# PFC_breakout_v2b.net
KiCad netlist of a schematic drawn in EAGLE
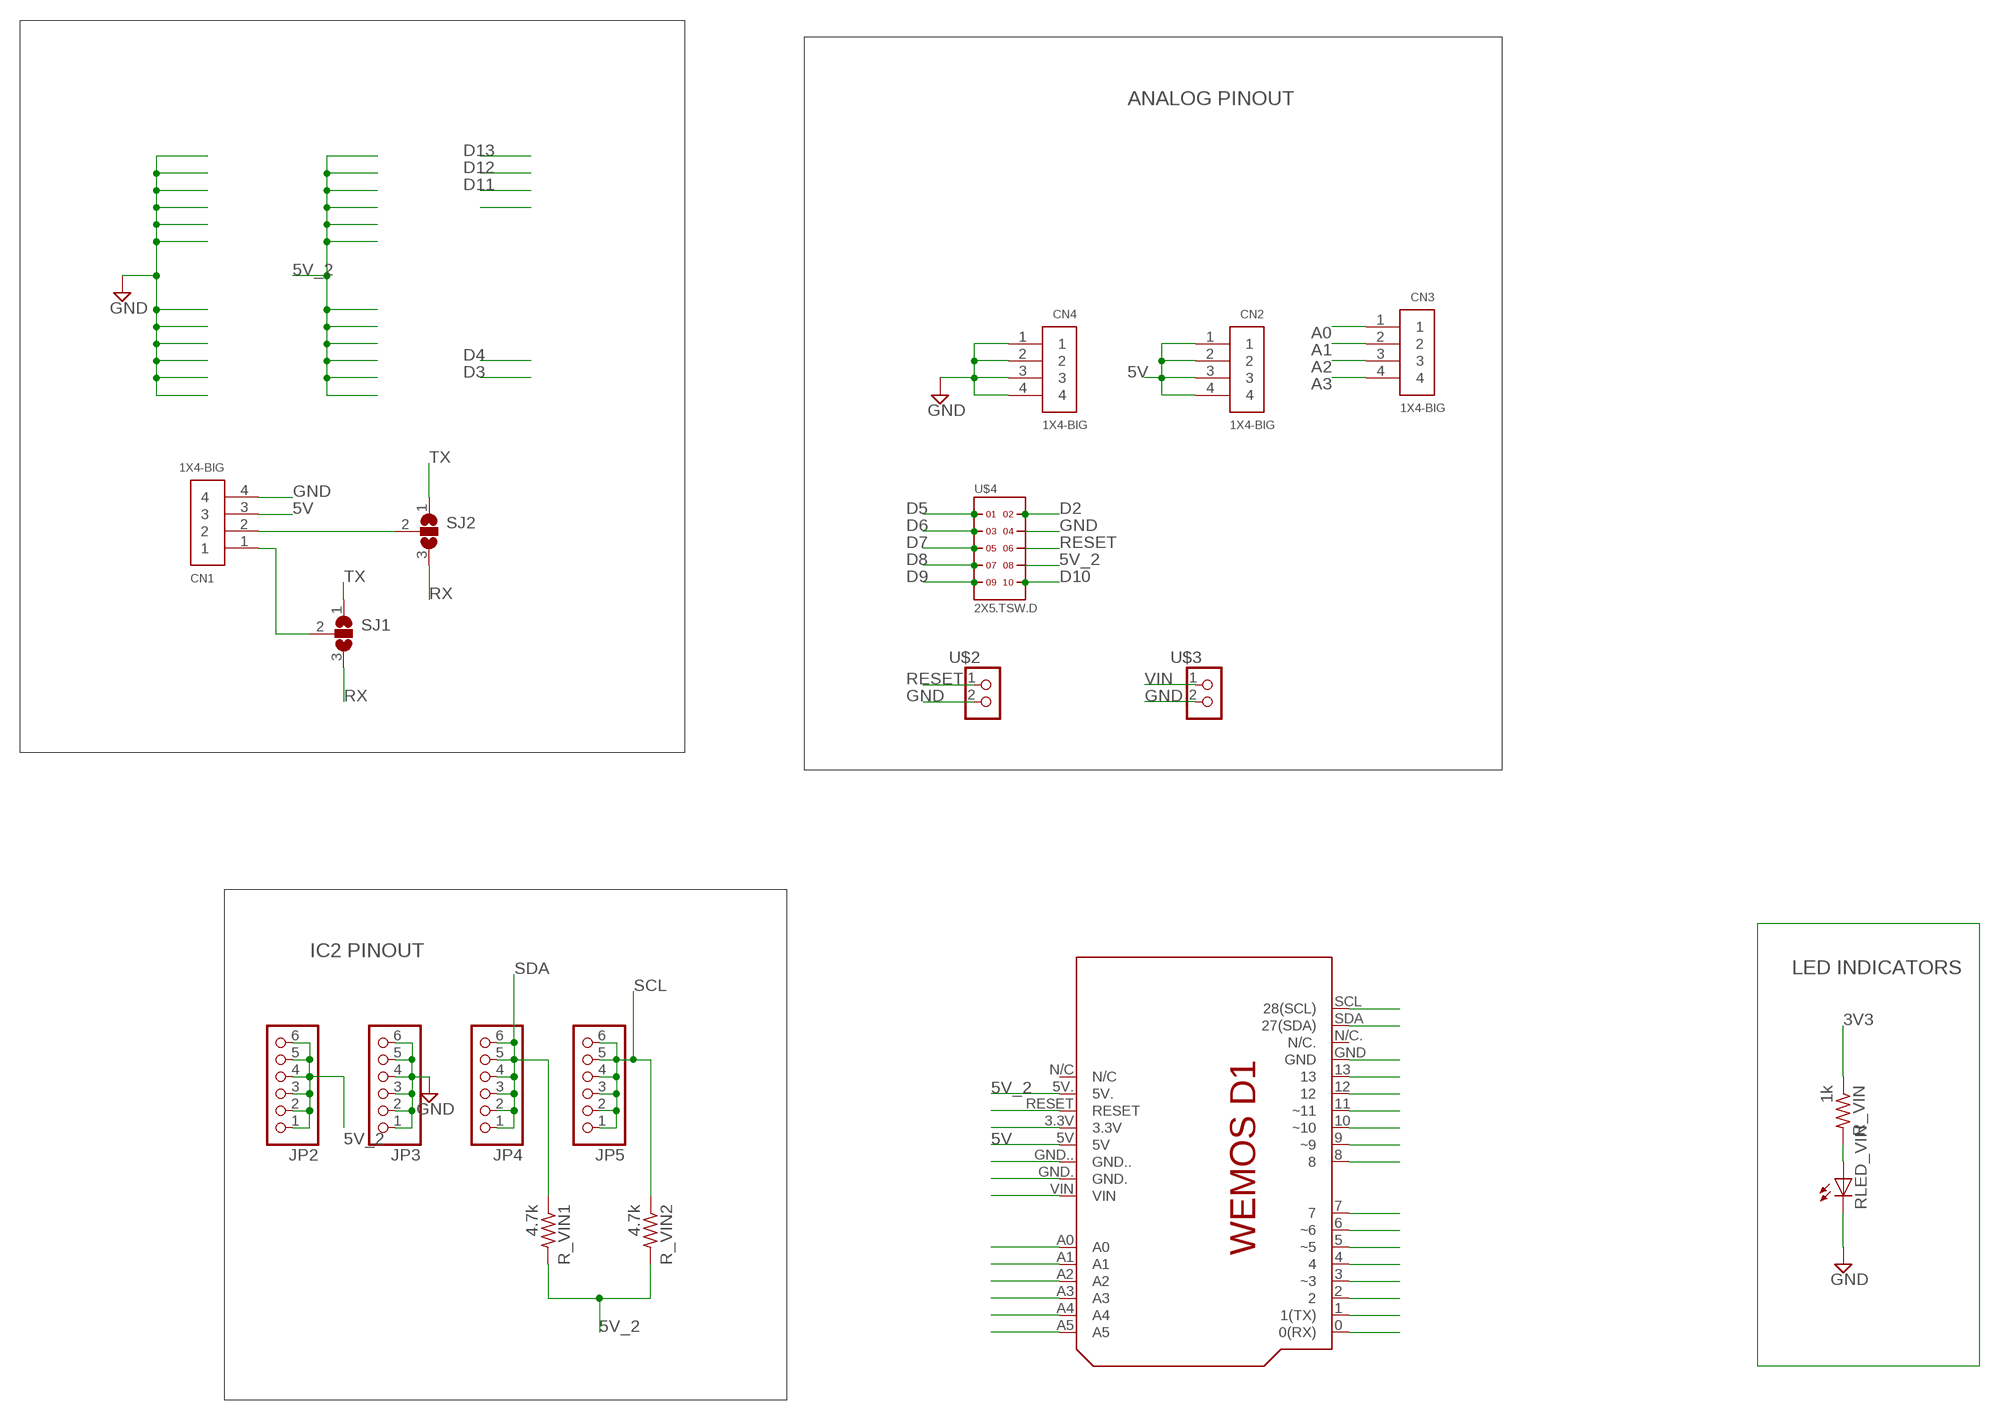
[diagram p0: schematic, sheet 1]

(export (version "E")
  (design (tool "Eeschema 10.0.6"))
  (components
    (comp (ref "CN1")
      (value "1X4-BIG")
      (footprint "eagle-import:1X04-BIG")
      (libsource (lib "eagle-import") (part "1X4-BIG"))
    )
    (comp (ref "CN2")
      (value "1X4-BIG")
      (footprint "eagle-import:1X04-BIG")
      (libsource (lib "eagle-import") (part "1X4-BIG"))
    )
    (comp (ref "CN3")
      (value "1X4-BIG")
      (footprint "eagle-import:1X04-BIG")
      (libsource (lib "eagle-import") (part "1X4-BIG"))
    )
    (comp (ref "CN4")
      (value "1X4-BIG")
      (footprint "eagle-import:1X04-BIG")
      (libsource (lib "eagle-import") (part "1X4-BIG"))
    )
    (comp (ref "JP2")
      (value "PINHD-1X6")
      (footprint "eagle-import:1X06")
      (libsource (lib "eagle-import") (part "PINHD-1X6"))
    )
    (comp (ref "JP3")
      (value "PINHD-1X6")
      (footprint "eagle-import:1X06")
      (libsource (lib "eagle-import") (part "PINHD-1X6"))
    )
    (comp (ref "JP4")
      (value "PINHD-1X6")
      (footprint "eagle-import:1X06")
      (libsource (lib "eagle-import") (part "PINHD-1X6"))
    )
    (comp (ref "JP5")
      (value "PINHD-1X6")
      (footprint "eagle-import:1X06")
      (libsource (lib "eagle-import") (part "PINHD-1X6"))
    )
    (comp (ref "RLED_VIN")
      (value "LEDCHIP-LED0603")
      (footprint "eagle-import:CHIP-LED0603")
      (libsource (lib "eagle-import") (part "LEDCHIP-LED0603"))
    )
    (comp (ref "R_VIN")
      (value "1k")
      (footprint "eagle-import:R0603")
      (libsource (lib "eagle-import") (part "R-US_R0603"))
    )
    (comp (ref "R_VIN1")
      (value "4.7k")
      (footprint "eagle-import:R0603")
      (libsource (lib "eagle-import") (part "R-US_R0603"))
    )
    (comp (ref "R_VIN2")
      (value "4.7k")
      (footprint "eagle-import:R0603")
      (libsource (lib "eagle-import") (part "R-US_R0603"))
    )
    (comp (ref "SJ1")
      (value "SJ2W")
      (footprint "eagle-import:SJ_2")
      (libsource (lib "eagle-import") (part "SJ2W"))
    )
    (comp (ref "SJ2")
      (value "SJ2W")
      (footprint "eagle-import:SJ_2")
      (libsource (lib "eagle-import") (part "SJ2W"))
    )
    (comp (ref "U$1")
      (value "WEMOS-D1SHIELD")
      (footprint "eagle-import:WEMOS-D1")
      (libsource (lib "eagle-import") (part "WEMOS-D1SHIELD"))
    )
    (comp (ref "U$2")
      (value "PINHD-2X1")
      (footprint "eagle-import:2X01")
      (libsource (lib "eagle-import") (part "PINHD-2X1"))
    )
    (comp (ref "U$3")
      (value "PINHD-2X1")
      (footprint "eagle-import:2X01")
      (libsource (lib "eagle-import") (part "PINHD-2X1"))
    )
    (comp (ref "U$4")
      (value "2X5.TSW.D")
      (footprint "eagle-import:TSW-105-XXX-D-XXX")
      (libsource (lib "eagle-import") (part "2X5.TSW.D"))
    )
  )
  (nets
    (net (code "1") (name "/3V3") (class "Default")
      (node (ref "R_VIN") (pin "1") (pinfunction "1_1") (pintype "passive"))
      (node (ref "U$1") (pin "3.3V") (pinfunction "3.3V_3.3V") (pintype "bidirectional"))
    )
    (net (code "2") (name "/5V") (class "Default")
      (node (ref "CN1") (pin "3") (pinfunction "3_3") (pintype "bidirectional"))
      (node (ref "CN2") (pin "1") (pinfunction "1_1") (pintype "bidirectional"))
      (node (ref "CN2") (pin "2") (pinfunction "2_2") (pintype "bidirectional"))
      (node (ref "CN2") (pin "3") (pinfunction "3_3") (pintype "bidirectional"))
      (node (ref "CN2") (pin "4") (pinfunction "4_4") (pintype "bidirectional"))
      (node (ref "U$1") (pin "5V") (pinfunction "5V_5V") (pintype "bidirectional"))
    )
    (net (code "3") (name "/5V_2") (class "Default")
      (node (ref "JP2") (pin "1") (pinfunction "1_1") (pintype "passive"))
      (node (ref "JP2") (pin "2") (pinfunction "2_2") (pintype "passive"))
      (node (ref "JP2") (pin "3") (pinfunction "3_3") (pintype "passive"))
      (node (ref "JP2") (pin "4") (pinfunction "4_4") (pintype "passive"))
      (node (ref "JP2") (pin "5") (pinfunction "5_5") (pintype "passive"))
      (node (ref "JP2") (pin "6") (pinfunction "6_6") (pintype "passive"))
      (node (ref "R_VIN1") (pin "2") (pinfunction "2_2") (pintype "passive"))
      (node (ref "R_VIN2") (pin "2") (pinfunction "2_2") (pintype "passive"))
      (node (ref "U$1") (pin "5V.") (pinfunction "5V._5V.") (pintype "bidirectional"))
      (node (ref "U$4") (pin "8") (pinfunction "8_8") (pintype "bidirectional"))
    )
    (net (code "4") (name "/A0") (class "Default")
      (node (ref "CN3") (pin "1") (pinfunction "1_1") (pintype "bidirectional"))
      (node (ref "U$1") (pin "A0") (pinfunction "A0_A0") (pintype "bidirectional"))
    )
    (net (code "5") (name "/A1") (class "Default")
      (node (ref "CN3") (pin "2") (pinfunction "2_2") (pintype "bidirectional"))
      (node (ref "U$1") (pin "A1") (pinfunction "A1_A1") (pintype "bidirectional"))
    )
    (net (code "6") (name "/A2") (class "Default")
      (node (ref "CN3") (pin "3") (pinfunction "3_3") (pintype "bidirectional"))
      (node (ref "U$1") (pin "A2") (pinfunction "A2_A2") (pintype "bidirectional"))
    )
    (net (code "7") (name "/A3") (class "Default")
      (node (ref "CN3") (pin "4") (pinfunction "4_4") (pintype "bidirectional"))
      (node (ref "U$1") (pin "A3") (pinfunction "A3_A3") (pintype "bidirectional"))
    )
    (net (code "8") (name "/D2") (class "Default")
      (node (ref "U$1") (pin "2") (pinfunction "2_2") (pintype "bidirectional"))
      (node (ref "U$4") (pin "2") (pinfunction "2_2") (pintype "bidirectional"))
    )
    (net (code "9") (name "/D3") (class "Default")
      (node (ref "U$1") (pin "3") (pinfunction "~{3}_3") (pintype "bidirectional"))
    )
    (net (code "10") (name "/D4") (class "Default")
      (node (ref "U$1") (pin "4") (pinfunction "4_4") (pintype "bidirectional"))
    )
    (net (code "11") (name "/D5") (class "Default")
      (node (ref "U$1") (pin "5") (pinfunction "~{5}_5") (pintype "bidirectional"))
      (node (ref "U$4") (pin "1") (pinfunction "1_1") (pintype "bidirectional"))
    )
    (net (code "12") (name "/D6") (class "Default")
      (node (ref "U$1") (pin "6") (pinfunction "~{6}_6") (pintype "bidirectional"))
      (node (ref "U$4") (pin "3") (pinfunction "3_3") (pintype "bidirectional"))
    )
    (net (code "13") (name "/D7") (class "Default")
      (node (ref "U$1") (pin "7") (pinfunction "7_7") (pintype "bidirectional"))
      (node (ref "U$4") (pin "5") (pinfunction "5_5") (pintype "bidirectional"))
    )
    (net (code "14") (name "/D8") (class "Default")
      (node (ref "U$1") (pin "8") (pinfunction "8_8") (pintype "bidirectional"))
      (node (ref "U$4") (pin "7") (pinfunction "7_7") (pintype "bidirectional"))
    )
    (net (code "15") (name "/D9") (class "Default")
      (node (ref "U$1") (pin "9") (pinfunction "~{9}_9") (pintype "bidirectional"))
      (node (ref "U$4") (pin "9") (pinfunction "9_9") (pintype "bidirectional"))
    )
    (net (code "16") (name "/D10") (class "Default")
      (node (ref "U$1") (pin "10") (pinfunction "~{10}_10") (pintype "bidirectional"))
      (node (ref "U$4") (pin "10") (pinfunction "10_10") (pintype "bidirectional"))
    )
    (net (code "17") (name "/D11") (class "Default")
      (node (ref "U$1") (pin "11") (pinfunction "~{11}_11") (pintype "bidirectional"))
    )
    (net (code "18") (name "/D12") (class "Default")
      (node (ref "U$1") (pin "12") (pinfunction "12_12") (pintype "bidirectional"))
    )
    (net (code "19") (name "/D13") (class "Default")
      (node (ref "U$1") (pin "13") (pinfunction "13_13") (pintype "bidirectional"))
    )
    (net (code "20") (name "/RESET") (class "Default")
      (node (ref "U$1") (pin "RESET") (pinfunction "RESET_RESET") (pintype "bidirectional"))
      (node (ref "U$2") (pin "1") (pinfunction "1_1") (pintype "passive"))
      (node (ref "U$4") (pin "6") (pinfunction "6_6") (pintype "bidirectional"))
    )
    (net (code "21") (name "/RX") (class "Default")
      (node (ref "SJ1") (pin "3") (pinfunction "3_3") (pintype "passive"))
      (node (ref "SJ2") (pin "3") (pinfunction "3_3") (pintype "passive"))
      (node (ref "U$1") (pin "0") (pinfunction "0(RX)_0") (pintype "bidirectional"))
    )
    (net (code "22") (name "/SCL") (class "Default")
      (node (ref "JP5") (pin "1") (pinfunction "1_1") (pintype "passive"))
      (node (ref "JP5") (pin "2") (pinfunction "2_2") (pintype "passive"))
      (node (ref "JP5") (pin "3") (pinfunction "3_3") (pintype "passive"))
      (node (ref "JP5") (pin "4") (pinfunction "4_4") (pintype "passive"))
      (node (ref "JP5") (pin "5") (pinfunction "5_5") (pintype "passive"))
      (node (ref "JP5") (pin "6") (pinfunction "6_6") (pintype "passive"))
      (node (ref "R_VIN2") (pin "1") (pinfunction "1_1") (pintype "passive"))
      (node (ref "U$1") (pin "SCL") (pinfunction "28(SCL)_SCL") (pintype "bidirectional"))
    )
    (net (code "23") (name "/SDA") (class "Default")
      (node (ref "JP4") (pin "1") (pinfunction "1_1") (pintype "passive"))
      (node (ref "JP4") (pin "2") (pinfunction "2_2") (pintype "passive"))
      (node (ref "JP4") (pin "3") (pinfunction "3_3") (pintype "passive"))
      (node (ref "JP4") (pin "4") (pinfunction "4_4") (pintype "passive"))
      (node (ref "JP4") (pin "5") (pinfunction "5_5") (pintype "passive"))
      (node (ref "JP4") (pin "6") (pinfunction "6_6") (pintype "passive"))
      (node (ref "R_VIN1") (pin "1") (pinfunction "1_1") (pintype "passive"))
      (node (ref "U$1") (pin "SDA") (pinfunction "27(SDA)_SDA") (pintype "bidirectional"))
    )
    (net (code "24") (name "/TX") (class "Default")
      (node (ref "SJ1") (pin "1") (pinfunction "1_1") (pintype "passive"))
      (node (ref "SJ2") (pin "1") (pinfunction "1_1") (pintype "passive"))
      (node (ref "U$1") (pin "1") (pinfunction "1(TX)_1") (pintype "bidirectional"))
    )
    (net (code "25") (name "/VIN") (class "Default")
      (node (ref "U$1") (pin "VIN") (pinfunction "VIN_VIN") (pintype "bidirectional"))
      (node (ref "U$3") (pin "1") (pinfunction "1_1") (pintype "passive"))
    )
    (net (code "26") (name "GND") (class "Default")
      (node (ref "CN1") (pin "4") (pinfunction "4_4") (pintype "bidirectional"))
      (node (ref "CN4") (pin "1") (pinfunction "1_1") (pintype "bidirectional"))
      (node (ref "CN4") (pin "2") (pinfunction "2_2") (pintype "bidirectional"))
      (node (ref "CN4") (pin "3") (pinfunction "3_3") (pintype "bidirectional"))
      (node (ref "CN4") (pin "4") (pinfunction "4_4") (pintype "bidirectional"))
      (node (ref "JP3") (pin "1") (pinfunction "1_1") (pintype "passive"))
      (node (ref "JP3") (pin "2") (pinfunction "2_2") (pintype "passive"))
      (node (ref "JP3") (pin "3") (pinfunction "3_3") (pintype "passive"))
      (node (ref "JP3") (pin "4") (pinfunction "4_4") (pintype "passive"))
      (node (ref "JP3") (pin "5") (pinfunction "5_5") (pintype "passive"))
      (node (ref "JP3") (pin "6") (pinfunction "6_6") (pintype "passive"))
      (node (ref "RLED_VIN") (pin "C") (pinfunction "C_C") (pintype "passive"))
      (node (ref "U$1") (pin "GND") (pinfunction "GND_GND") (pintype "bidirectional"))
      (node (ref "U$1") (pin "GND.") (pinfunction "GND._GND.") (pintype "bidirectional"))
      (node (ref "U$1") (pin "GND..") (pinfunction "GND.._GND..") (pintype "bidirectional"))
      (node (ref "U$2") (pin "2") (pinfunction "3_2") (pintype "passive"))
      (node (ref "U$3") (pin "2") (pinfunction "3_2") (pintype "passive"))
      (node (ref "U$4") (pin "4") (pinfunction "4_4") (pintype "bidirectional"))
    )
    (net (code "27") (name "Net-(CN1-Pad1)") (class "Default")
      (node (ref "CN1") (pin "1") (pinfunction "1_1") (pintype "bidirectional"))
      (node (ref "SJ1") (pin "2") (pinfunction "2_2") (pintype "passive"))
    )
    (net (code "28") (name "Net-(CN1-Pad2)") (class "Default")
      (node (ref "CN1") (pin "2") (pinfunction "2_2") (pintype "bidirectional"))
      (node (ref "SJ2") (pin "2") (pinfunction "2_2") (pintype "passive"))
    )
    (net (code "29") (name "Net-(RLED_VIN-PadA)") (class "Default")
      (node (ref "RLED_VIN") (pin "A") (pinfunction "A_A") (pintype "passive"))
      (node (ref "R_VIN") (pin "2") (pinfunction "2_2") (pintype "passive"))
    )
    (net (code "30") (name "unconnected-(U$1-PadA4)") (class "Default")
      (node (ref "U$1") (pin "A4") (pinfunction "A4_A4") (pintype "bidirectional"))
    )
    (net (code "31") (name "unconnected-(U$1-PadA5)") (class "Default")
      (node (ref "U$1") (pin "A5") (pinfunction "A5_A5") (pintype "bidirectional"))
    )
    (net (code "32") (name "unconnected-(U$1-PadN{slash}C)") (class "Default")
      (node (ref "U$1") (pin "N/C") (pinfunction "N/C_N/C") (pintype "bidirectional"))
    )
    (net (code "33") (name "unconnected-(U$1-PadN{slash}C.)") (class "Default")
      (node (ref "U$1") (pin "N/C.") (pinfunction "N/C._N/C.") (pintype "bidirectional"))
    )
  )
)
